# Input.net
KiCad netlist of a schematic drawn in EAGLE
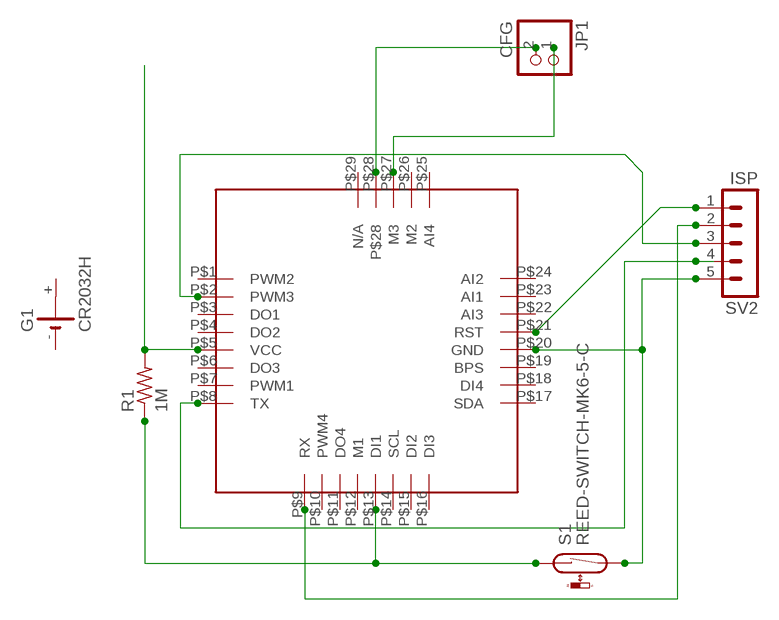
[diagram p0: schematic, sheet 1]

(export (version "E")
  (design (tool "Eeschema 10.0.6"))
  (components
    (comp (ref "G1")
      (value "CR2032H")
      (footprint "eagle-import:CR2032H")
      (libsource (lib "eagle-import") (part "CR2032H"))
    )
    (comp (ref "JP1")
      (value "CFG")
      (footprint "eagle-import:1X02")
      (libsource (lib "eagle-import") (part "PINHD-1X2"))
    )
    (comp (ref "R1")
      (value "1M")
      (footprint "eagle-import:V234_12")
      (libsource (lib "eagle-import") (part "R-US_V234/12"))
    )
    (comp (ref "S1")
      (value "REED-SWITCH-MK6-5-C")
      (footprint "eagle-import:MK6-5")
      (fields (field (name "MF") "MEDER") (field (name "MPN") "MK6-5-C"))
      (libsource (lib "eagle-import") (part "REED-SWITCH-MK6-5-C"))
    )
    (comp (ref "SV2")
      (value "ISP")
      (footprint "eagle-import:MA05-1")
      (libsource (lib "eagle-import") (part "MA05-1"))
    )
    (comp (ref "U$1")
      (value "LITE")
      (footprint "eagle-import:LITE")
      (libsource (lib "eagle-import") (part "LITE"))
    )
  )
  (nets
    (net (code "1") (name "Net-(JP1-Pad2)") (class "Default")
      (node (ref "JP1") (pin "2") (pinfunction "2_2") (pintype "passive"))
      (node (ref "U$1") (pin "P$28") (pinfunction "P$28_P$28") (pintype "bidirectional"))
    )
    (net (code "2") (name "Net-(U$1-DI1)") (class "Default")
      (node (ref "R1") (pin "1") (pinfunction "1_1") (pintype "passive"))
      (node (ref "S1") (pin "1") (pinfunction "1_1") (pintype "passive"))
      (node (ref "U$1") (pin "P$13") (pinfunction "DI1_P$13") (pintype "bidirectional"))
    )
    (net (code "3") (name "Net-(U$1-GND)") (class "Default")
      (node (ref "S1") (pin "2") (pinfunction "2_2") (pintype "passive"))
      (node (ref "SV2") (pin "5") (pinfunction "5_5") (pintype "passive"))
      (node (ref "U$1") (pin "P$20") (pinfunction "GND_P$20") (pintype "bidirectional"))
    )
    (net (code "4") (name "Net-(U$1-M3)") (class "Default")
      (node (ref "JP1") (pin "1") (pinfunction "1_1") (pintype "passive"))
      (node (ref "U$1") (pin "P$27") (pinfunction "M3_P$27") (pintype "bidirectional"))
    )
    (net (code "5") (name "Net-(U$1-PWM3)") (class "Default")
      (node (ref "SV2") (pin "3") (pinfunction "3_3") (pintype "passive"))
      (node (ref "U$1") (pin "P$2") (pinfunction "PWM3_P$2") (pintype "bidirectional"))
    )
    (net (code "6") (name "Net-(U$1-RST)") (class "Default")
      (node (ref "SV2") (pin "1") (pinfunction "1_1") (pintype "passive"))
      (node (ref "U$1") (pin "P$21") (pinfunction "RST_P$21") (pintype "bidirectional"))
    )
    (net (code "7") (name "Net-(U$1-RX)") (class "Default")
      (node (ref "SV2") (pin "2") (pinfunction "2_2") (pintype "passive"))
      (node (ref "U$1") (pin "P$9") (pinfunction "RX_P$9") (pintype "bidirectional"))
    )
    (net (code "8") (name "Net-(U$1-TX)") (class "Default")
      (node (ref "SV2") (pin "4") (pinfunction "4_4") (pintype "passive"))
      (node (ref "U$1") (pin "P$8") (pinfunction "TX_P$8") (pintype "bidirectional"))
    )
    (net (code "9") (name "Net-(U$1-VCC)") (class "Default")
      (node (ref "R1") (pin "2") (pinfunction "2_2") (pintype "passive"))
      (node (ref "U$1") (pin "P$5") (pinfunction "VCC_P$5") (pintype "bidirectional"))
    )
    (net (code "10") (name "unconnected-(G1-+-Pad+@1)") (class "Default")
      (node (ref "G1") (pin "+@1") (pinfunction "+_+@1") (pintype "passive"))
    )
    (net (code "11") (name "unconnected-(G1-Pad+)") (class "Default")
      (node (ref "G1") (pin "+") (pinfunction "+_+") (pintype "passive"))
    )
    (net (code "12") (name "unconnected-(G1-Pad-)") (class "Default")
      (node (ref "G1") (pin "-") (pinfunction "-_-") (pintype "passive"))
    )
    (net (code "13") (name "unconnected-(U$1-AI1-PadP$23)") (class "Default")
      (node (ref "U$1") (pin "P$23") (pinfunction "AI1_P$23") (pintype "bidirectional"))
    )
    (net (code "14") (name "unconnected-(U$1-AI2-PadP$24)") (class "Default")
      (node (ref "U$1") (pin "P$24") (pinfunction "AI2_P$24") (pintype "bidirectional"))
    )
    (net (code "15") (name "unconnected-(U$1-AI3-PadP$22)") (class "Default")
      (node (ref "U$1") (pin "P$22") (pinfunction "AI3_P$22") (pintype "bidirectional"))
    )
    (net (code "16") (name "unconnected-(U$1-AI4-PadP$25)") (class "Default")
      (node (ref "U$1") (pin "P$25") (pinfunction "AI4_P$25") (pintype "bidirectional"))
    )
    (net (code "17") (name "unconnected-(U$1-BPS-PadP$19)") (class "Default")
      (node (ref "U$1") (pin "P$19") (pinfunction "BPS_P$19") (pintype "bidirectional"))
    )
    (net (code "18") (name "unconnected-(U$1-DI2-PadP$15)") (class "Default")
      (node (ref "U$1") (pin "P$15") (pinfunction "DI2_P$15") (pintype "bidirectional"))
    )
    (net (code "19") (name "unconnected-(U$1-DI3-PadP$16)") (class "Default")
      (node (ref "U$1") (pin "P$16") (pinfunction "DI3_P$16") (pintype "bidirectional"))
    )
    (net (code "20") (name "unconnected-(U$1-DI4-PadP$18)") (class "Default")
      (node (ref "U$1") (pin "P$18") (pinfunction "DI4_P$18") (pintype "bidirectional"))
    )
    (net (code "21") (name "unconnected-(U$1-DO1-PadP$3)") (class "Default")
      (node (ref "U$1") (pin "P$3") (pinfunction "DO1_P$3") (pintype "bidirectional"))
    )
    (net (code "22") (name "unconnected-(U$1-DO2-PadP$4)") (class "Default")
      (node (ref "U$1") (pin "P$4") (pinfunction "DO2_P$4") (pintype "bidirectional"))
    )
    (net (code "23") (name "unconnected-(U$1-DO3-PadP$6)") (class "Default")
      (node (ref "U$1") (pin "P$6") (pinfunction "DO3_P$6") (pintype "bidirectional"))
    )
    (net (code "24") (name "unconnected-(U$1-DO4-PadP$11)") (class "Default")
      (node (ref "U$1") (pin "P$11") (pinfunction "DO4_P$11") (pintype "bidirectional"))
    )
    (net (code "25") (name "unconnected-(U$1-M1-PadP$12)") (class "Default")
      (node (ref "U$1") (pin "P$12") (pinfunction "M1_P$12") (pintype "bidirectional"))
    )
    (net (code "26") (name "unconnected-(U$1-M2-PadP$26)") (class "Default")
      (node (ref "U$1") (pin "P$26") (pinfunction "M2_P$26") (pintype "bidirectional"))
    )
    (net (code "27") (name "unconnected-(U$1-N{slash}A-PadP$29)") (class "Default")
      (node (ref "U$1") (pin "P$29") (pinfunction "N/A_P$29") (pintype "bidirectional"))
    )
    (net (code "28") (name "unconnected-(U$1-PWM1-PadP$7)") (class "Default")
      (node (ref "U$1") (pin "P$7") (pinfunction "PWM1_P$7") (pintype "bidirectional"))
    )
    (net (code "29") (name "unconnected-(U$1-PWM2-PadP$1)") (class "Default")
      (node (ref "U$1") (pin "P$1") (pinfunction "PWM2_P$1") (pintype "bidirectional"))
    )
    (net (code "30") (name "unconnected-(U$1-PWM4-PadP$10)") (class "Default")
      (node (ref "U$1") (pin "P$10") (pinfunction "PWM4_P$10") (pintype "bidirectional"))
    )
    (net (code "31") (name "unconnected-(U$1-SCL-PadP$14)") (class "Default")
      (node (ref "U$1") (pin "P$14") (pinfunction "SCL_P$14") (pintype "bidirectional"))
    )
    (net (code "32") (name "unconnected-(U$1-SDA-PadP$17)") (class "Default")
      (node (ref "U$1") (pin "P$17") (pinfunction "SDA_P$17") (pintype "bidirectional"))
    )
  )
)
